# Peripherals.net
KiCad netlist of a schematic drawn in Altium Designer
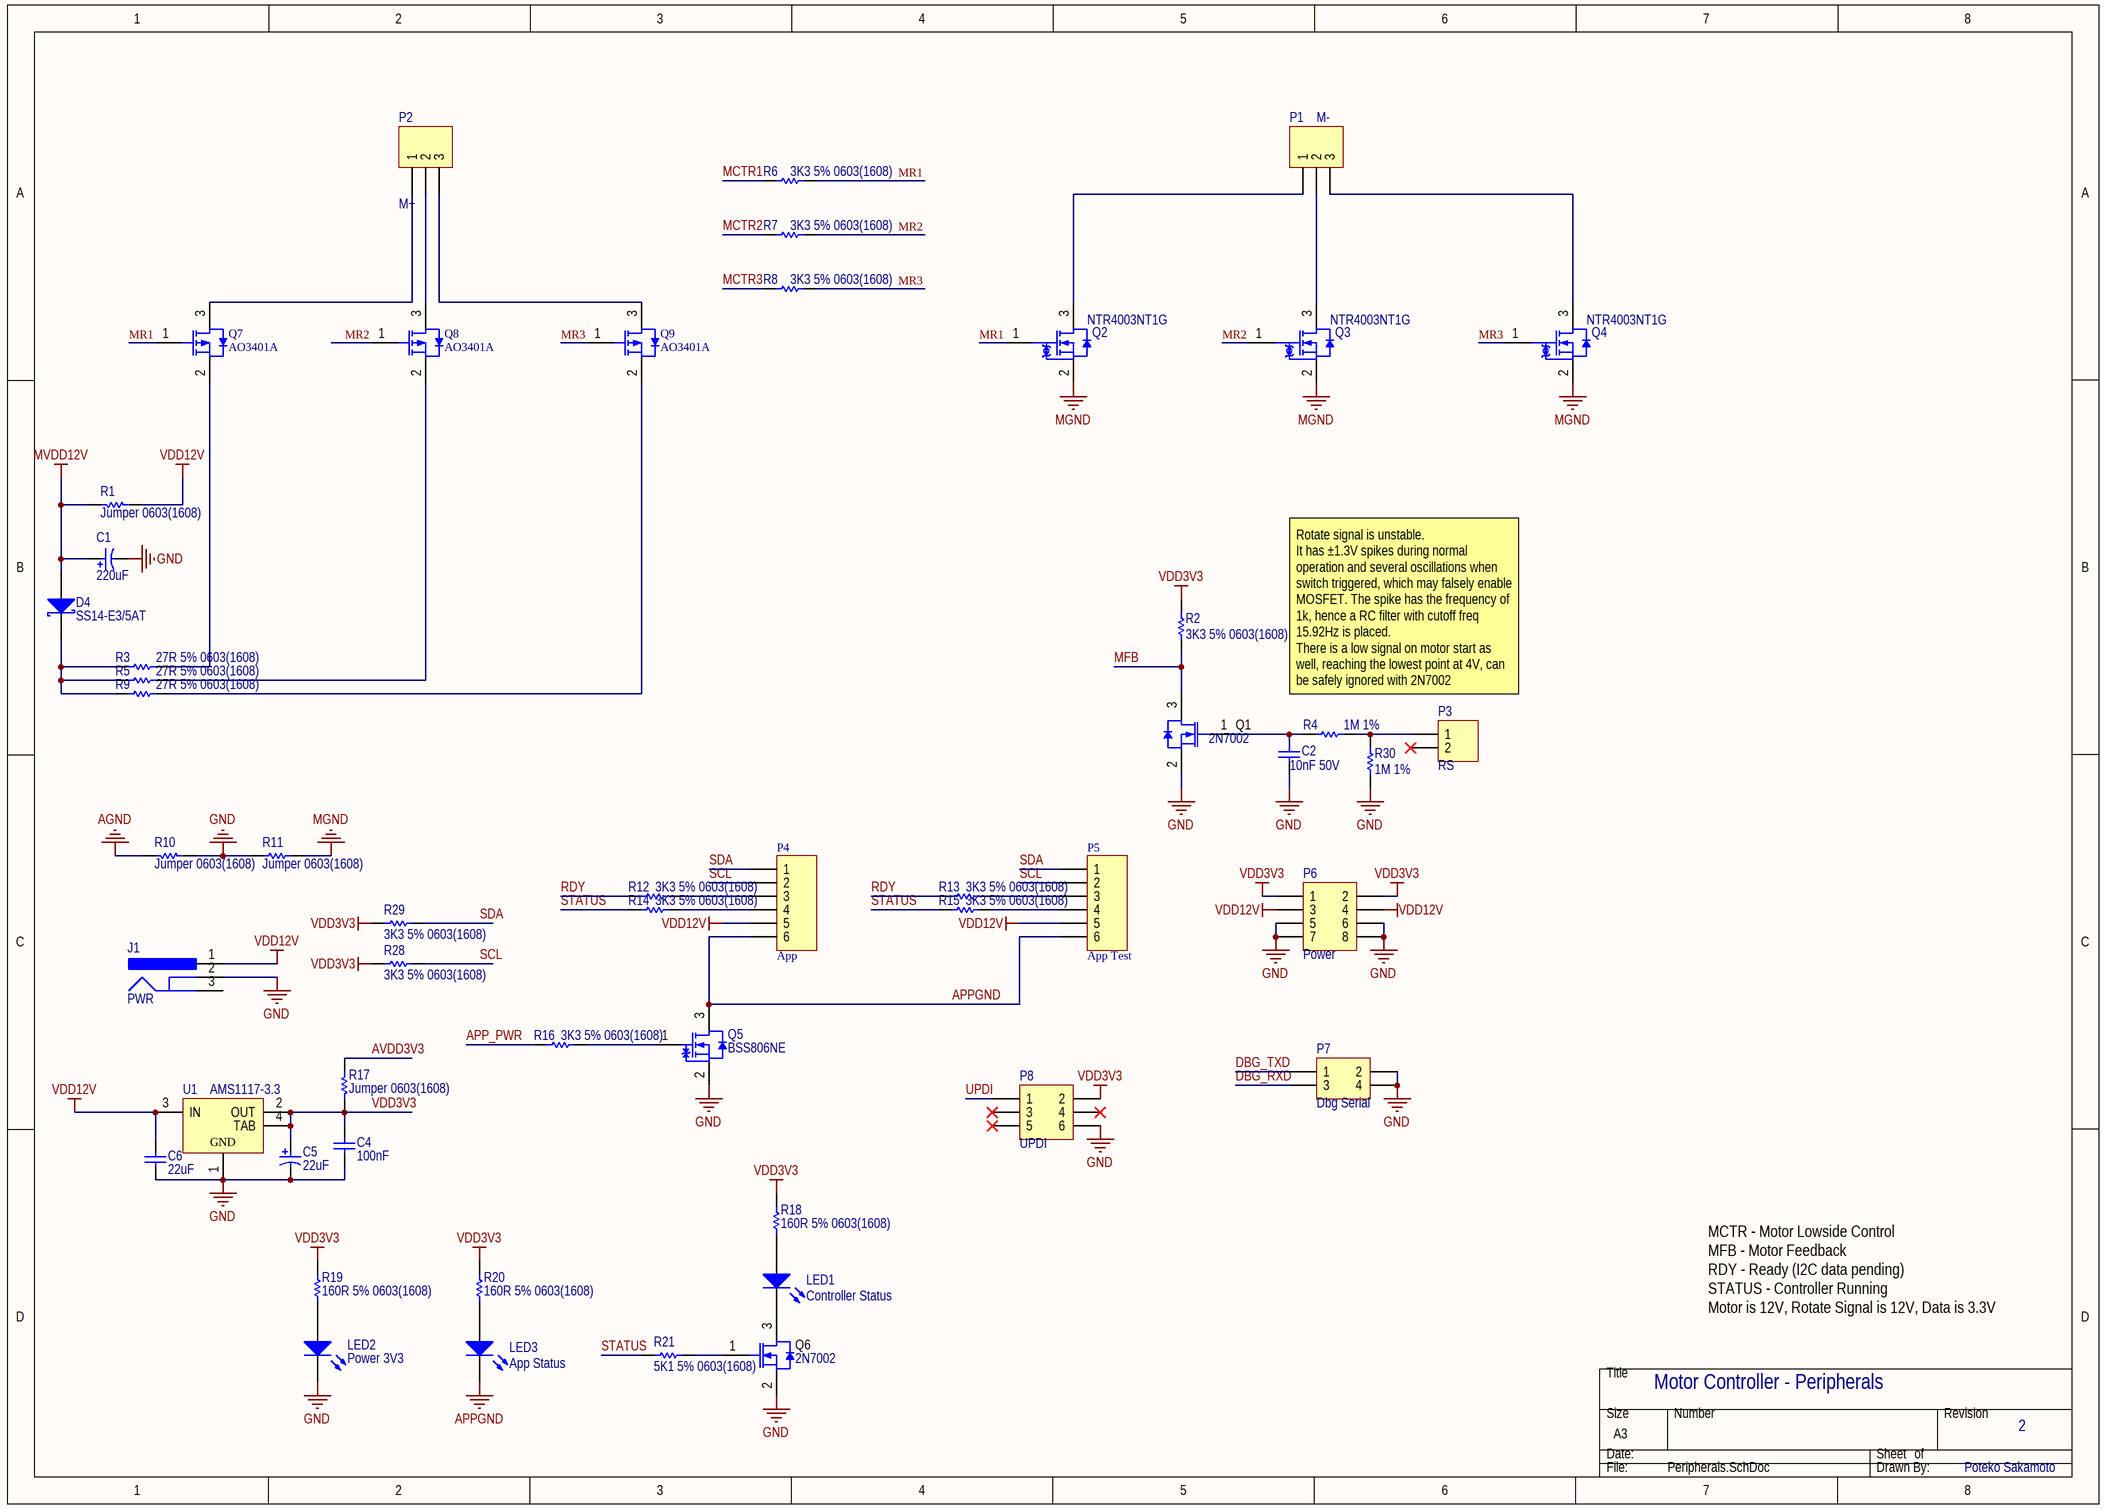
[diagram p0: Peripherals.SchDoc]

(export (version "E")
  (design (tool "Eeschema 10.0.6"))
  (components
    (comp (ref "C1")
      (value "220uF")
      (footprint "PNSC-ZA-G_M")
      (fields (field (name "TOLERANCE") "20%") (field (name "MANUFACTURER") "Panasonic"))
      (libsource (lib "Altium Content Vault") (part "CAP-P-2"))
    )
    (comp (ref "C2")
      (value "10nF 50V")
      (footprint "CAPC0603(1608)100_M")
      (description "CAP 10nF 50V ±5% 0603 (1608 Metric) Thickness 1mm SMD")
      (fields (field (name "TOLERANCE") "Â±5%"))
      (libsource (lib "Altium Content Vault") (part "CAP"))
    )
    (comp (ref "C4")
      (value "100nF")
      (footprint "CAPC0603(1608)100_M")
      (description "CAP 100nF 50V ±10% 0603 (1608 Metric) Thickness 1mm SMD")
      (fields (field (name "TOLERANCE") "Â±10%"))
      (libsource (lib "Altium Content Vault") (part "CAP"))
    )
    (comp (ref "C5")
      (value "22uF")
      (footprint "KEMT-A-3216-18-2_M")
      (description "Capacitor, Tantalum, 22 uF, +/- 10%, 16 V, -55 to 125 degC, 2-Pin SMD (1206), RoHS, Tape and Reel")
      (fields (field (name "VOLTAGE") "16VDC") (field (name "MANUFACTURER") "Kemet"))
      (libsource (lib "Altium Content Vault") (part "CAP-P-2"))
    )
    (comp (ref "C6")
      (value "22uF")
      (footprint "CAPC0805(2012)145_M")
      (description "CAP 22uF 10V ±10% 0805 (2012 Metric) Thickness 1.45mm SMD")
      (fields (field (name "TOLERANCE") "Â±10%"))
      (libsource (lib "Altium Content Vault") (part "CAP"))
    )
    (comp (ref "D4")
      (value "SS14-E3/5AT")
      (footprint "VISH-DO-214AC-2_V")
      (fields (field (name "MANUFACTURER") "Vishay Semiconductor"))
      (libsource (lib "Altium Content Vault") (part "VISH-DSKY_A1K2-2"))
    )
    (comp (ref "J1")
      (value "PWR")
      (footprint "KYCN-KLDX-0202-A_V")
      (description "DC Power Jack, 24 V, 3.5 A, -25 to 85 degC, 3-Pin THD, RoHS")
      (fields (field (name "MANUFACTURER") "Kycon"))
      (libsource (lib "Altium Content Vault") (part "JACK-2CD3-RN"))
    )
    (comp (ref "LED1")
      (value "Controller Status")
      (footprint "0805_A")
      (description "SMD mono-color Chip LED, WL-SMCW, Blue")
      (fields (field (name "MANUFACTURER") "Wuerth Elektronik") (field (name "PARTNUMBER") "150080BS75000"))
      (libsource (lib "Altium Content Vault") (part "WE-LED_K1A2-2"))
    )
    (comp (ref "LED2")
      (value "Power 3V3")
      (footprint "0805_A")
      (description "SMD mono-color Chip LED, WL-SMCW, Green")
      (fields (field (name "PARTNUMBER") "150080GS75000") (field (name "MANUFACTURER") "Wuerth Elektronik"))
      (libsource (lib "Altium Content Vault") (part "WE-LED_K1A2-2"))
    )
    (comp (ref "LED3")
      (value "App Status")
      (footprint "0805_A")
      (description "SMD mono-color Chip LED, WL-SMCW, Blue")
      (fields (field (name "MANUFACTURER") "Wuerth Elektronik") (field (name "PARTNUMBER") "150080BS75000"))
      (libsource (lib "Altium Content Vault") (part "WE-LED_K1A2-2"))
    )
    (comp (ref "P1")
      (value "M-")
      (footprint "HDR1X3")
      (description "Header, 3-Pin")
      (fields (field (name "PUBLISHER") "Altium Limited"))
      (libsource (lib "Miscellaneous Connectors") (part "Header 3"))
    )
    (comp (ref "P2")
      (value "M+")
      (footprint "HDR1X3")
      (description "Header, 3-Pin")
      (fields (field (name "PUBLISHER") "Altium Limited"))
      (libsource (lib "Miscellaneous Connectors") (part "Header 3"))
    )
    (comp (ref "P3")
      (value "RS")
      (footprint "HDR1X2")
      (description "Header, 2-Pin")
      (fields (field (name "PUBLISHER") "Altium Limited"))
      (libsource (lib "Miscellaneous Connectors") (part "Header 2"))
    )
    (comp (ref "P4")
      (value "App")
      (footprint "PH2.0-WS-6P")
      (description "Header, 6-Pin")
      (fields (field (name "PUBLISHER") "Altium Limited"))
      (libsource (lib "Miscellaneous Connectors") (part "Header 6"))
    )
    (comp (ref "P5")
      (value "App Test")
      (footprint "Miscellaneous Connectors:HDR1X6")
      (description "Header, 6-Pin")
      (fields (field (name "PUBLISHER") "Altium Limited"))
      (libsource (lib "Miscellaneous Connectors") (part "Header 6"))
    )
    (comp (ref "P6")
      (value "Power")
      (footprint "HDR2X4")
      (description "Header, 4-Pin, Dual row")
      (fields (field (name "PUBLISHER") "Altium Limited"))
      (libsource (lib "Miscellaneous Connectors") (part "Header 4X2"))
    )
    (comp (ref "P7")
      (value "Dbg Serial")
      (footprint "HDR2X2")
      (description "Header, 2-Pin, Dual row")
      (fields (field (name "PUBLISHER") "Altium Limited"))
      (libsource (lib "Miscellaneous Connectors") (part "Header 2X2"))
    )
    (comp (ref "P8")
      (value "UPDI")
      (footprint "HDR2X3")
      (description "Header, 3-Pin, Dual row")
      (fields (field (name "PUBLISHER") "Altium Limited"))
      (libsource (lib "Miscellaneous Connectors") (part "Header 3X2"))
    )
    (comp (ref "Q1")
      (value "2N7002")
      (footprint "INF-PG-SOT23_M")
      (fields (field (name "MANUFACTURER") "Infineon"))
      (libsource (lib "Altium Content Vault") (part "INF-NDMOS-GSD-3"))
    )
    (comp (ref "Q2")
      (value "NTR4003NT1G")
      (footprint "ONSC-SOT-23-3-318-08_V")
      (description "Small Signal MOSFET, 30 V, 0.56 A, Single N-Channe, 3-Pin SOT-23, Pb-Free, Tape and Reel")
      (fields (field (name "MANUFACTURER") "On Semiconductor"))
      (libsource (lib "Altium Content Vault") (part "ONSC-NMOS-G1S2D3-3_F"))
    )
    (comp (ref "Q3")
      (value "NTR4003NT1G")
      (footprint "ONSC-SOT-23-3-318-08_V")
      (description "Small Signal MOSFET, 30 V, 0.56 A, Single N-Channe, 3-Pin SOT-23, Pb-Free, Tape and Reel")
      (fields (field (name "MANUFACTURER") "On Semiconductor"))
      (libsource (lib "Altium Content Vault") (part "ONSC-NMOS-G1S2D3-3_F"))
    )
    (comp (ref "Q4")
      (value "NTR4003NT1G")
      (footprint "ONSC-SOT-23-3-318-08_V")
      (description "Small Signal MOSFET, 30 V, 0.56 A, Single N-Channe, 3-Pin SOT-23, Pb-Free, Tape and Reel")
      (fields (field (name "MANUFACTURER") "On Semiconductor"))
      (libsource (lib "Altium Content Vault") (part "ONSC-NMOS-G1S2D3-3_F"))
    )
    (comp (ref "Q5")
      (value "BSS806NE")
      (footprint "INF-PG-SOT23-3_N")
      (fields (field (name "MANUFACTURER") "Infineon"))
      (libsource (lib "Altium Content Vault") (part "INF-NEMOS_GSD_ESD-3"))
    )
    (comp (ref "Q6")
      (value "2N7002")
      (footprint "INF-PG-SOT23_M")
      (fields (field (name "MANUFACTURER") "Infineon"))
      (libsource (lib "Altium Content Vault") (part "INF-NDMOS-GSD-3"))
    )
    (comp (ref "Q7")
      (value "AO3401A")
      (footprint "AO-SOT-23-3L_V")
      (description "P-Channel MOSFET, 30 V, 4 A, -55 to 150 degC, 3-Pin SOT-23-3L, RoHS, Tape and Reel")
      (fields (field (name "MANUFACTURER") "Alpha and Omega"))
      (libsource (lib "Altium Content Vault") (part "PEMOS-GSD-3"))
    )
    (comp (ref "Q8")
      (value "AO3401A")
      (footprint "AO-SOT-23-3L_V")
      (description "P-Channel MOSFET, 30 V, 4 A, -55 to 150 degC, 3-Pin SOT-23-3L, RoHS, Tape and Reel")
      (fields (field (name "MANUFACTURER") "Alpha and Omega"))
      (libsource (lib "Altium Content Vault") (part "PEMOS-GSD-3"))
    )
    (comp (ref "Q9")
      (value "AO3401A")
      (footprint "AO-SOT-23-3L_V")
      (description "P-Channel MOSFET, 30 V, 4 A, -55 to 150 degC, 3-Pin SOT-23-3L, RoHS, Tape and Reel")
      (fields (field (name "MANUFACTURER") "Alpha and Omega"))
      (libsource (lib "Altium Content Vault") (part "PEMOS-GSD-3"))
    )
    (comp (ref "R1")
      (value "Jumper 0603(1608)")
      (footprint "RESC0603(1608)_M")
      (description "Jumper 0603 (1608 Metric)")
      (fields (field (name "POWER") "None"))
      (libsource (lib "Altium Content Vault") (part "RES"))
    )
    (comp (ref "R2")
      (value "3K3 5% 0603(1608)")
      (footprint "RESC0603(1608)_M")
      (description "3K3 0.1W 5% 0603 (1608 Metric)  SMD")
      (fields (field (name "TOLERANCE") "5 %") (field (name "POWER") "0.1 W"))
      (libsource (lib "Altium Content Vault") (part "RES"))
    )
    (comp (ref "R3")
      (value "27R 5% 0603(1608)")
      (footprint "RESC0603(1608)_M")
      (description "27R 0.1W 5% 0603 (1608 Metric)  SMD")
      (fields (field (name "POWER") "0.1 W") (field (name "TOLERANCE") "5 %"))
      (libsource (lib "Altium Content Vault") (part "RES"))
    )
    (comp (ref "R4")
      (value "1M 1%")
      (footprint "RESC0603(1608)_M")
      (description "1M 0.1W 1% 0603 (1608 Metric)  SMD")
      (fields (field (name "POWER") "0.1 W") (field (name "TOLERANCE") "1 %"))
      (libsource (lib "Altium Content Vault") (part "RES"))
    )
    (comp (ref "R5")
      (value "27R 5% 0603(1608)")
      (footprint "RESC0603(1608)_M")
      (description "27R 0.1W 5% 0603 (1608 Metric)  SMD")
      (fields (field (name "POWER") "0.1 W") (field (name "TOLERANCE") "5 %"))
      (libsource (lib "Altium Content Vault") (part "RES"))
    )
    (comp (ref "R6")
      (value "3K3 5% 0603(1608)")
      (footprint "RESC0603(1608)_M")
      (description "3K3 0.1W 5% 0603 (1608 Metric)  SMD")
      (fields (field (name "TOLERANCE") "5 %") (field (name "POWER") "0.1 W"))
      (libsource (lib "Altium Content Vault") (part "RES"))
    )
    (comp (ref "R7")
      (value "3K3 5% 0603(1608)")
      (footprint "RESC0603(1608)_M")
      (description "3K3 0.1W 5% 0603 (1608 Metric)  SMD")
      (fields (field (name "TOLERANCE") "5 %") (field (name "POWER") "0.1 W"))
      (libsource (lib "Altium Content Vault") (part "RES"))
    )
    (comp (ref "R8")
      (value "3K3 5% 0603(1608)")
      (footprint "RESC0603(1608)_M")
      (description "3K3 0.1W 5% 0603 (1608 Metric)  SMD")
      (fields (field (name "TOLERANCE") "5 %") (field (name "POWER") "0.1 W"))
      (libsource (lib "Altium Content Vault") (part "RES"))
    )
    (comp (ref "R9")
      (value "27R 5% 0603(1608)")
      (footprint "RESC0603(1608)_M")
      (description "27R 0.1W 5% 0603 (1608 Metric)  SMD")
      (fields (field (name "POWER") "0.1 W") (field (name "TOLERANCE") "5 %"))
      (libsource (lib "Altium Content Vault") (part "RES"))
    )
    (comp (ref "R10")
      (value "Jumper 0603(1608)")
      (footprint "RESC0603(1608)_M")
      (description "Jumper 0603 (1608 Metric)")
      (fields (field (name "POWER") "None"))
      (libsource (lib "Altium Content Vault") (part "RES"))
    )
    (comp (ref "R11")
      (value "Jumper 0603(1608)")
      (footprint "RESC0603(1608)_M")
      (description "Jumper 0603 (1608 Metric)")
      (fields (field (name "POWER") "None"))
      (libsource (lib "Altium Content Vault") (part "RES"))
    )
    (comp (ref "R12")
      (value "3K3 5% 0603(1608)")
      (footprint "RESC0603(1608)_M")
      (description "3K3 0.1W 5% 0603 (1608 Metric)  SMD")
      (fields (field (name "TOLERANCE") "5 %") (field (name "POWER") "0.1 W"))
      (libsource (lib "Altium Content Vault") (part "RES"))
    )
    (comp (ref "R13")
      (value "3K3 5% 0603(1608)")
      (footprint "RESC0603(1608)_M")
      (description "3K3 0.1W 5% 0603 (1608 Metric)  SMD")
      (fields (field (name "TOLERANCE") "5 %") (field (name "POWER") "0.1 W"))
      (libsource (lib "Altium Content Vault") (part "RES"))
    )
    (comp (ref "R14")
      (value "3K3 5% 0603(1608)")
      (footprint "RESC0603(1608)_M")
      (description "3K3 0.1W 5% 0603 (1608 Metric)  SMD")
      (fields (field (name "TOLERANCE") "5 %") (field (name "POWER") "0.1 W"))
      (libsource (lib "Altium Content Vault") (part "RES"))
    )
    (comp (ref "R15")
      (value "3K3 5% 0603(1608)")
      (footprint "RESC0603(1608)_M")
      (description "3K3 0.1W 5% 0603 (1608 Metric)  SMD")
      (fields (field (name "TOLERANCE") "5 %") (field (name "POWER") "0.1 W"))
      (libsource (lib "Altium Content Vault") (part "RES"))
    )
    (comp (ref "R16")
      (value "3K3 5% 0603(1608)")
      (footprint "RESC0603(1608)_M")
      (description "3K3 0.1W 5% 0603 (1608 Metric)  SMD")
      (fields (field (name "TOLERANCE") "5 %") (field (name "POWER") "0.1 W"))
      (libsource (lib "Altium Content Vault") (part "RES"))
    )
    (comp (ref "R17")
      (value "Jumper 0603(1608)")
      (footprint "RESC0603(1608)_M")
      (description "Jumper 0603 (1608 Metric)")
      (fields (field (name "POWER") "None"))
      (libsource (lib "Altium Content Vault") (part "RES"))
    )
    (comp (ref "R18")
      (value "160R 5% 0603(1608)")
      (footprint "RESC0603(1608)_M")
      (description "160R 0.1W 5% 0603 (1608 Metric)  SMD")
      (fields (field (name "TOLERANCE") "5 %") (field (name "POWER") "0.1 W"))
      (libsource (lib "Altium Content Vault") (part "RES"))
    )
    (comp (ref "R19")
      (value "160R 5% 0603(1608)")
      (footprint "RESC0603(1608)_M")
      (description "160R 0.1W 5% 0603 (1608 Metric)  SMD")
      (fields (field (name "TOLERANCE") "5 %") (field (name "POWER") "0.1 W"))
      (libsource (lib "Altium Content Vault") (part "RES"))
    )
    (comp (ref "R20")
      (value "160R 5% 0603(1608)")
      (footprint "RESC0603(1608)_M")
      (description "160R 0.1W 5% 0603 (1608 Metric)  SMD")
      (fields (field (name "TOLERANCE") "5 %") (field (name "POWER") "0.1 W"))
      (libsource (lib "Altium Content Vault") (part "RES"))
    )
    (comp (ref "R21")
      (value "5K1 5% 0603(1608)")
      (footprint "RESC0603(1608)_M")
      (description "5K1 0.1W 5% 0603 (1608 Metric)  SMD")
      (fields (field (name "TOLERANCE") "5 %") (field (name "POWER") "0.1 W"))
      (libsource (lib "Altium Content Vault") (part "RES"))
    )
    (comp (ref "R28")
      (value "3K3 5% 0603(1608)")
      (footprint "RESC0603(1608)_M")
      (description "3K3 0.1W 5% 0603 (1608 Metric)  SMD")
      (fields (field (name "TOLERANCE") "5 %") (field (name "POWER") "0.1 W"))
      (libsource (lib "Altium Content Vault") (part "RES"))
    )
    (comp (ref "R29")
      (value "3K3 5% 0603(1608)")
      (footprint "RESC0603(1608)_M")
      (description "3K3 0.1W 5% 0603 (1608 Metric)  SMD")
      (fields (field (name "TOLERANCE") "5 %") (field (name "POWER") "0.1 W"))
      (libsource (lib "Altium Content Vault") (part "RES"))
    )
    (comp (ref "R30")
      (value "1M 1%")
      (footprint "RESC0603(1608)_M")
      (description "1M 0.1W 1% 0603 (1608 Metric)  SMD")
      (fields (field (name "POWER") "0.1 W") (field (name "TOLERANCE") "1 %"))
      (libsource (lib "Altium Content Vault") (part "RES"))
    )
    (comp (ref "U1")
      (value "AMS1117-3.3")
      (footprint "DCY0004A_M")
      (description "800mA Low-Dropout Linear Regulator, 4-pin SOT-223")
      (fields (field (name "PARTNUMBER") "LM1117MPX-3.3") (field (name "MANUFACTURER") "Texas Instruments"))
      (libsource (lib "Altium Content Vault") (part "PM-REG-LM1086-SOT4"))
    )
  )
  (nets
    (net (code "2") (name "/APP_PWR") (class "Default")
      (node (ref "R16") (pin "2") (pinfunction "2_2") (pintype "passive"))
    )
    (net (code "3") (name "/AVDD3V3") (class "Default")
      (node (ref "R17") (pin "1") (pinfunction "1_1") (pintype "passive"))
    )
    (net (code "4") (name "/DBG_RXD") (class "Default")
      (node (ref "P7") (pin "3") (pinfunction "3_3") (pintype "passive"))
    )
    (net (code "5") (name "/DBG_TXD") (class "Default")
      (node (ref "P7") (pin "1") (pinfunction "1_1") (pintype "passive"))
    )
    (net (code "6") (name "/MCTR1") (class "Default")
      (node (ref "R6") (pin "2") (pinfunction "2_2") (pintype "passive"))
    )
    (net (code "7") (name "/MCTR2") (class "Default")
      (node (ref "R7") (pin "2") (pinfunction "2_2") (pintype "passive"))
    )
    (net (code "8") (name "/MCTR3") (class "Default")
      (node (ref "R8") (pin "2") (pinfunction "2_2") (pintype "passive"))
    )
    (net (code "9") (name "/MFB") (class "Default")
      (node (ref "Q1") (pin "3") (pinfunction "DRAIN_3") (pintype "passive"))
      (node (ref "R2") (pin "2") (pinfunction "2_2") (pintype "passive"))
    )
    (net (code "10") (name "/MR1") (class "Default")
      (node (ref "Q2") (pin "1") (pinfunction "G_1") (pintype "passive"))
      (node (ref "Q7") (pin "1") (pinfunction "GATE_1") (pintype "passive"))
      (node (ref "R6") (pin "1") (pinfunction "1_1") (pintype "passive"))
    )
    (net (code "11") (name "/MR2") (class "Default")
      (node (ref "Q3") (pin "1") (pinfunction "G_1") (pintype "passive"))
      (node (ref "Q8") (pin "1") (pinfunction "GATE_1") (pintype "passive"))
      (node (ref "R7") (pin "1") (pinfunction "1_1") (pintype "passive"))
    )
    (net (code "12") (name "/MR3") (class "Default")
      (node (ref "Q4") (pin "1") (pinfunction "G_1") (pintype "passive"))
      (node (ref "Q9") (pin "1") (pinfunction "GATE_1") (pintype "passive"))
      (node (ref "R8") (pin "1") (pinfunction "1_1") (pintype "passive"))
    )
    (net (code "13") (name "/RDY") (class "Default")
      (node (ref "R12") (pin "2") (pinfunction "2_2") (pintype "passive"))
      (node (ref "R13") (pin "2") (pinfunction "2_2") (pintype "passive"))
    )
    (net (code "14") (name "/SCL") (class "Default")
      (node (ref "P4") (pin "2") (pinfunction "2_2") (pintype "passive"))
      (node (ref "P5") (pin "2") (pinfunction "2_2") (pintype "passive"))
      (node (ref "R28") (pin "2") (pinfunction "2_2") (pintype "passive"))
    )
    (net (code "15") (name "/SDA") (class "Default")
      (node (ref "P4") (pin "1") (pinfunction "1_1") (pintype "passive"))
      (node (ref "P5") (pin "1") (pinfunction "1_1") (pintype "passive"))
      (node (ref "R29") (pin "2") (pinfunction "2_2") (pintype "passive"))
    )
    (net (code "16") (name "/STATUS") (class "Default")
      (node (ref "R14") (pin "2") (pinfunction "2_2") (pintype "passive"))
      (node (ref "R15") (pin "2") (pinfunction "2_2") (pintype "passive"))
      (node (ref "R21") (pin "1") (pinfunction "1_1") (pintype "passive"))
    )
    (net (code "17") (name "/UPDI") (class "Default")
      (node (ref "P8") (pin "1") (pinfunction "1_1") (pintype "passive"))
    )
    (net (code "18") (name "AGND") (class "Default")
      (node (ref "R10") (pin "2") (pinfunction "2_2") (pintype "passive"))
    )
    (net (code "19") (name "APPGND") (class "Default")
      (node (ref "LED3") (pin "1") (pinfunction "K_1") (pintype "passive"))
      (node (ref "P4") (pin "6") (pinfunction "6_6") (pintype "passive"))
      (node (ref "P5") (pin "6") (pinfunction "6_6") (pintype "passive"))
      (node (ref "Q5") (pin "3") (pinfunction "DRAIN_3") (pintype "passive"))
    )
    (net (code "20") (name "GND") (class "Default")
      (node (ref "C1") (pin "2") (pinfunction "2_2") (pintype "passive"))
      (node (ref "C2") (pin "1") (pinfunction "1_1") (pintype "passive"))
      (node (ref "C4") (pin "1") (pinfunction "1_1") (pintype "passive"))
      (node (ref "C5") (pin "2") (pinfunction "2_2") (pintype "passive"))
      (node (ref "C6") (pin "1") (pinfunction "1_1") (pintype "passive"))
      (node (ref "J1") (pin "2") (pinfunction "2_2") (pintype "passive"))
      (node (ref "LED2") (pin "1") (pinfunction "K_1") (pintype "passive"))
      (node (ref "P6") (pin "5") (pinfunction "5_5") (pintype "passive"))
      (node (ref "P6") (pin "6") (pinfunction "6_6") (pintype "passive"))
      (node (ref "P6") (pin "7") (pinfunction "7_7") (pintype "passive"))
      (node (ref "P6") (pin "8") (pinfunction "8_8") (pintype "passive"))
      (node (ref "P7") (pin "2") (pinfunction "2_2") (pintype "passive"))
      (node (ref "P7") (pin "4") (pinfunction "4_4") (pintype "passive"))
      (node (ref "P8") (pin "6") (pinfunction "6_6") (pintype "passive"))
      (node (ref "Q1") (pin "2") (pinfunction "SOURCE_2") (pintype "passive"))
      (node (ref "Q5") (pin "2") (pinfunction "SOURCE_2") (pintype "passive"))
      (node (ref "Q6") (pin "2") (pinfunction "SOURCE_2") (pintype "passive"))
      (node (ref "R10") (pin "1") (pinfunction "1_1") (pintype "passive"))
      (node (ref "R11") (pin "1") (pinfunction "1_1") (pintype "passive"))
      (node (ref "R30") (pin "1") (pinfunction "1_1") (pintype "passive"))
      (node (ref "U1") (pin "1") (pinfunction "GND_1") (pintype "power_in"))
    )
    (net (code "21") (name "MGND") (class "Default")
      (node (ref "Q2") (pin "2") (pinfunction "S_2") (pintype "passive"))
      (node (ref "Q3") (pin "2") (pinfunction "S_2") (pintype "passive"))
      (node (ref "Q4") (pin "2") (pinfunction "S_2") (pintype "passive"))
      (node (ref "R11") (pin "2") (pinfunction "2_2") (pintype "passive"))
    )
    (net (code "22") (name "MVDD12V") (class "Default")
      (node (ref "C1") (pin "1") (pinfunction "1_1") (pintype "passive"))
      (node (ref "D4") (pin "1") (pinfunction "A_1") (pintype "passive"))
      (node (ref "R1") (pin "2") (pinfunction "2_2") (pintype "passive"))
    )
    (net (code "23") (name "Net-(D4-K)") (class "Default")
      (node (ref "D4") (pin "2") (pinfunction "K_2") (pintype "passive"))
      (node (ref "R3") (pin "1") (pinfunction "1_1") (pintype "passive"))
      (node (ref "R5") (pin "1") (pinfunction "1_1") (pintype "passive"))
      (node (ref "R9") (pin "1") (pinfunction "1_1") (pintype "passive"))
    )
    (net (code "24") (name "Net-(LED1-A)") (class "Default")
      (node (ref "LED1") (pin "2") (pinfunction "A_2") (pintype "passive"))
      (node (ref "R18") (pin "1") (pinfunction "1_1") (pintype "passive"))
    )
    (net (code "25") (name "Net-(LED1-K)") (class "Default")
      (node (ref "LED1") (pin "1") (pinfunction "K_1") (pintype "passive"))
      (node (ref "Q6") (pin "3") (pinfunction "DRAIN_3") (pintype "passive"))
    )
    (net (code "26") (name "Net-(LED2-A)") (class "Default")
      (node (ref "LED2") (pin "2") (pinfunction "A_2") (pintype "passive"))
      (node (ref "R19") (pin "1") (pinfunction "1_1") (pintype "passive"))
    )
    (net (code "27") (name "Net-(LED3-A)") (class "Default")
      (node (ref "LED3") (pin "2") (pinfunction "A_2") (pintype "passive"))
      (node (ref "R20") (pin "1") (pinfunction "1_1") (pintype "passive"))
    )
    (net (code "28") (name "Net-(P3-Pad1)") (class "Default")
      (node (ref "P3") (pin "1") (pinfunction "1_1") (pintype "passive"))
      (node (ref "R30") (pin "2") (pinfunction "2_2") (pintype "passive"))
      (node (ref "R4") (pin "2") (pinfunction "2_2") (pintype "passive"))
    )
    (net (code "29") (name "Net-(P4-Pad3)") (class "Default")
      (node (ref "P4") (pin "3") (pinfunction "3_3") (pintype "passive"))
      (node (ref "R12") (pin "1") (pinfunction "1_1") (pintype "passive"))
    )
    (net (code "30") (name "Net-(P4-Pad4)") (class "Default")
      (node (ref "P4") (pin "4") (pinfunction "4_4") (pintype "passive"))
      (node (ref "R14") (pin "1") (pinfunction "1_1") (pintype "passive"))
    )
    (net (code "31") (name "Net-(P5-Pad3)") (class "Default")
      (node (ref "P5") (pin "3") (pinfunction "3_3") (pintype "passive"))
      (node (ref "R13") (pin "1") (pinfunction "1_1") (pintype "passive"))
    )
    (net (code "32") (name "Net-(P5-Pad4)") (class "Default")
      (node (ref "P5") (pin "4") (pinfunction "4_4") (pintype "passive"))
      (node (ref "R15") (pin "1") (pinfunction "1_1") (pintype "passive"))
    )
    (net (code "33") (name "Net-(Q1-GATE)") (class "Default")
      (node (ref "C2") (pin "2") (pinfunction "2_2") (pintype "passive"))
      (node (ref "Q1") (pin "1") (pinfunction "GATE_1") (pintype "passive"))
      (node (ref "R4") (pin "1") (pinfunction "1_1") (pintype "passive"))
    )
    (net (code "34") (name "Net-(Q2-D)") (class "Default")
      (node (ref "P1") (pin "1") (pinfunction "1_1") (pintype "passive"))
      (node (ref "Q2") (pin "3") (pinfunction "D_3") (pintype "passive"))
    )
    (net (code "35") (name "Net-(Q3-D)") (class "Default")
      (node (ref "P1") (pin "2") (pinfunction "2_2") (pintype "passive"))
      (node (ref "Q3") (pin "3") (pinfunction "D_3") (pintype "passive"))
    )
    (net (code "36") (name "Net-(Q4-D)") (class "Default")
      (node (ref "P1") (pin "3") (pinfunction "3_3") (pintype "passive"))
      (node (ref "Q4") (pin "3") (pinfunction "D_3") (pintype "passive"))
    )
    (net (code "37") (name "Net-(Q5-GATE)") (class "Default")
      (node (ref "Q5") (pin "1") (pinfunction "GATE_1") (pintype "passive"))
      (node (ref "R16") (pin "1") (pinfunction "1_1") (pintype "passive"))
    )
    (net (code "38") (name "Net-(Q6-GATE)") (class "Default")
      (node (ref "Q6") (pin "1") (pinfunction "GATE_1") (pintype "passive"))
      (node (ref "R21") (pin "2") (pinfunction "2_2") (pintype "passive"))
    )
    (net (code "39") (name "Net-(Q7-DRAIN)") (class "Default")
      (node (ref "P2") (pin "1") (pinfunction "1_1") (pintype "passive"))
      (node (ref "Q7") (pin "3") (pinfunction "DRAIN_3") (pintype "passive"))
    )
    (net (code "40") (name "Net-(Q7-SOURCE)") (class "Default")
      (node (ref "Q7") (pin "2") (pinfunction "SOURCE_2") (pintype "passive"))
      (node (ref "R3") (pin "2") (pinfunction "2_2") (pintype "passive"))
    )
    (net (code "41") (name "Net-(Q8-DRAIN)") (class "Default")
      (node (ref "P2") (pin "2") (pinfunction "2_2") (pintype "passive"))
      (node (ref "Q8") (pin "3") (pinfunction "DRAIN_3") (pintype "passive"))
    )
    (net (code "42") (name "Net-(Q8-SOURCE)") (class "Default")
      (node (ref "Q8") (pin "2") (pinfunction "SOURCE_2") (pintype "passive"))
      (node (ref "R5") (pin "2") (pinfunction "2_2") (pintype "passive"))
    )
    (net (code "43") (name "Net-(Q9-DRAIN)") (class "Default")
      (node (ref "P2") (pin "3") (pinfunction "3_3") (pintype "passive"))
      (node (ref "Q9") (pin "3") (pinfunction "DRAIN_3") (pintype "passive"))
    )
    (net (code "44") (name "Net-(Q9-SOURCE)") (class "Default")
      (node (ref "Q9") (pin "2") (pinfunction "SOURCE_2") (pintype "passive"))
      (node (ref "R9") (pin "2") (pinfunction "2_2") (pintype "passive"))
    )
    (net (code "45") (name "VDD3V3") (class "Default")
      (node (ref "C4") (pin "2") (pinfunction "2_2") (pintype "passive"))
      (node (ref "C5") (pin "1") (pinfunction "1_1") (pintype "passive"))
      (node (ref "P6") (pin "1") (pinfunction "1_1") (pintype "passive"))
      (node (ref "P6") (pin "2") (pinfunction "2_2") (pintype "passive"))
      (node (ref "P8") (pin "2") (pinfunction "2_2") (pintype "passive"))
      (node (ref "R17") (pin "2") (pinfunction "2_2") (pintype "passive"))
      (node (ref "R18") (pin "2") (pinfunction "2_2") (pintype "passive"))
      (node (ref "R19") (pin "2") (pinfunction "2_2") (pintype "passive"))
      (node (ref "R2") (pin "1") (pinfunction "1_1") (pintype "passive"))
      (node (ref "R20") (pin "2") (pinfunction "2_2") (pintype "passive"))
      (node (ref "R28") (pin "1") (pinfunction "1_1") (pintype "passive"))
      (node (ref "R29") (pin "1") (pinfunction "1_1") (pintype "passive"))
      (node (ref "U1") (pin "2") (pinfunction "OUT_2") (pintype "power_in"))
      (node (ref "U1") (pin "4") (pinfunction "TAB_4") (pintype "power_in"))
    )
    (net (code "46") (name "VDD12V") (class "Default")
      (node (ref "C6") (pin "2") (pinfunction "2_2") (pintype "passive"))
      (node (ref "J1") (pin "1") (pinfunction "1_1") (pintype "passive"))
      (node (ref "P4") (pin "5") (pinfunction "5_5") (pintype "passive"))
      (node (ref "P5") (pin "5") (pinfunction "5_5") (pintype "passive"))
      (node (ref "P6") (pin "3") (pinfunction "3_3") (pintype "passive"))
      (node (ref "P6") (pin "4") (pinfunction "4_4") (pintype "passive"))
      (node (ref "R1") (pin "1") (pinfunction "1_1") (pintype "passive"))
      (node (ref "U1") (pin "3") (pinfunction "IN_3") (pintype "power_in"))
    )
    (net (code "47") (name "unconnected-(J1-Pad3)") (class "Default")
      (node (ref "J1") (pin "3") (pinfunction "3_3") (pintype "passive"))
    )
    (net (code "48") (name "unconnected-(P3-Pad2)") (class "Default")
      (node (ref "P3") (pin "2") (pinfunction "2_2") (pintype "passive+no_connect"))
    )
    (net (code "49") (name "unconnected-(P8-Pad3)") (class "Default")
      (node (ref "P8") (pin "3") (pinfunction "3_3") (pintype "passive+no_connect"))
    )
    (net (code "50") (name "unconnected-(P8-Pad4)") (class "Default")
      (node (ref "P8") (pin "4") (pinfunction "4_4") (pintype "passive+no_connect"))
    )
    (net (code "51") (name "unconnected-(P8-Pad5)") (class "Default")
      (node (ref "P8") (pin "5") (pinfunction "5_5") (pintype "passive+no_connect"))
    )
  )
)
